# box.net
KiCad netlist of a schematic drawn in EAGLE
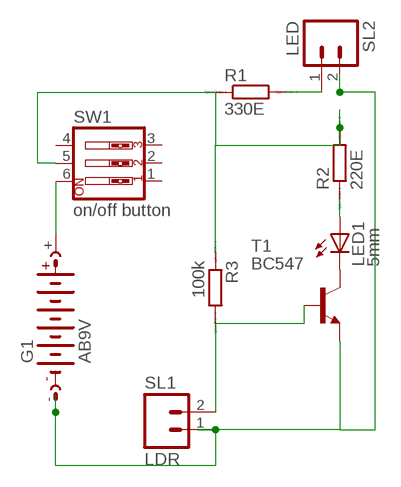
[diagram p0: schematic, sheet 1]

(export (version "E")
  (design (tool "Eeschema 10.0.6"))
  (components
    (comp (ref "G1")
      (value "AB9V")
      (footprint "eagle-import:AB9V")
      (libsource (lib "eagle-import") (part "AB9V"))
    )
    (comp (ref "LED1")
      (value "5mm")
      (footprint "eagle-import:LED5MM")
      (libsource (lib "eagle-import") (part "LED5MM"))
    )
    (comp (ref "R1")
      (value "330E")
      (footprint "eagle-import:0204_7")
      (libsource (lib "eagle-import") (part "R0204/7"))
    )
    (comp (ref "R2")
      (value "220E")
      (footprint "eagle-import:0204_7")
      (libsource (lib "eagle-import") (part "R0204/7"))
    )
    (comp (ref "R3")
      (value "100k")
      (footprint "eagle-import:0204_7")
      (libsource (lib "eagle-import") (part "R0204/7"))
    )
    (comp (ref "SL1")
      (value "LDR")
      (footprint "eagle-import:02P")
      (libsource (lib "eagle-import") (part "M02"))
    )
    (comp (ref "SL2")
      (value "LED")
      (footprint "eagle-import:02P")
      (libsource (lib "eagle-import") (part "M02"))
    )
    (comp (ref "SW1")
      (value "on/off button")
      (footprint "eagle-import:EDG-03")
      (libsource (lib "eagle-import") (part "SW_DIP-3"))
    )
    (comp (ref "T1")
      (value "BC547")
      (footprint "eagle-import:TO92")
      (libsource (lib "eagle-import") (part "BC547"))
    )
  )
  (nets
    (net (code "1") (name "Net-(G1-Pad+)") (class "Default")
      (node (ref "G1") (pin "+") (pinfunction "+_+") (pintype "passive"))
      (node (ref "SW1") (pin "6") (pinfunction "6_6") (pintype "passive"))
    )
    (net (code "2") (name "Net-(LED1-C)") (class "Default")
      (node (ref "LED1") (pin "K") (pinfunction "C_K") (pintype "passive"))
      (node (ref "T1") (pin "3") (pinfunction "C_3") (pintype "passive"))
    )
    (net (code "3") (name "Net-(LED1-PadA)") (class "Default")
      (node (ref "LED1") (pin "A") (pinfunction "A_A") (pintype "passive"))
      (node (ref "R2") (pin "1") (pinfunction "1_1") (pintype "passive"))
    )
    (net (code "4") (name "Net-(R1-Pad1)") (class "Default")
      (node (ref "R1") (pin "1") (pinfunction "1_1") (pintype "passive"))
      (node (ref "R2") (pin "2") (pinfunction "2_2") (pintype "passive"))
      (node (ref "R3") (pin "1") (pinfunction "1_1") (pintype "passive"))
      (node (ref "SW1") (pin "5") (pinfunction "5_5") (pintype "passive"))
    )
    (net (code "5") (name "Net-(R1-Pad2)") (class "Default")
      (node (ref "R1") (pin "2") (pinfunction "2_2") (pintype "passive"))
      (node (ref "SL2") (pin "1") (pinfunction "1_1") (pintype "passive"))
    )
    (net (code "6") (name "Net-(T1-B)") (class "Default")
      (node (ref "R3") (pin "2") (pinfunction "2_2") (pintype "passive"))
      (node (ref "SL1") (pin "2") (pinfunction "2_2") (pintype "passive"))
      (node (ref "T1") (pin "2") (pinfunction "B_2") (pintype "passive"))
    )
    (net (code "7") (name "Net-(T1-E)") (class "Default")
      (node (ref "G1") (pin "-") (pinfunction "-_-") (pintype "passive"))
      (node (ref "SL1") (pin "1") (pinfunction "1_1") (pintype "passive"))
      (node (ref "SL2") (pin "2") (pinfunction "2_2") (pintype "passive"))
      (node (ref "T1") (pin "1") (pinfunction "E_1") (pintype "passive"))
    )
    (net (code "8") (name "unconnected-(SW1-Pad1)") (class "Default")
      (node (ref "SW1") (pin "1") (pinfunction "1_1") (pintype "passive"))
    )
    (net (code "9") (name "unconnected-(SW1-Pad2)") (class "Default")
      (node (ref "SW1") (pin "2") (pinfunction "2_2") (pintype "passive"))
    )
    (net (code "10") (name "unconnected-(SW1-Pad3)") (class "Default")
      (node (ref "SW1") (pin "3") (pinfunction "3_3") (pintype "passive"))
    )
    (net (code "11") (name "unconnected-(SW1-Pad4)") (class "Default")
      (node (ref "SW1") (pin "4") (pinfunction "4_4") (pintype "passive"))
    )
  )
)
